# PCB-BI16-1x4.net
KiCad netlist of a schematic drawn in EAGLE
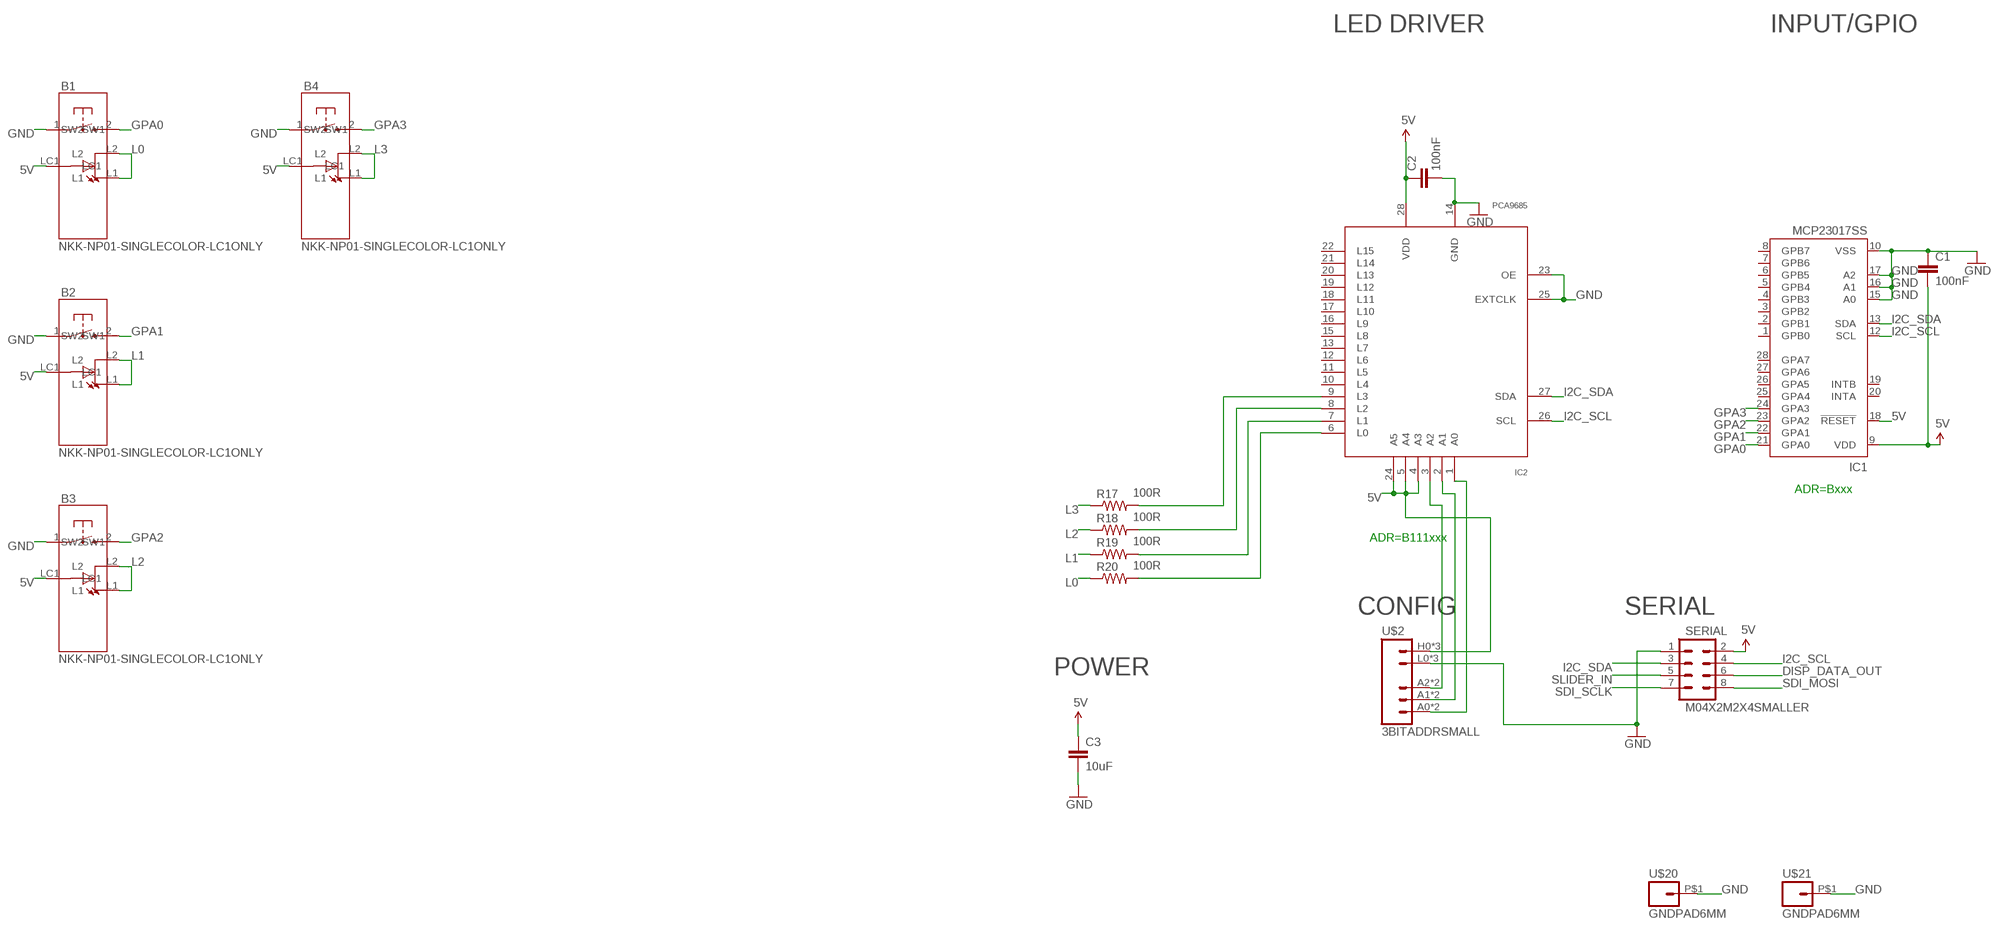
[diagram p0: schematic, sheet 1]

(export (version "E")
  (design (tool "Eeschema 10.0.6"))
  (components
    (comp (ref "B1")
      (value "NKK-NP01-SINGLECOLOR-LC1ONLY")
      (footprint "eagle-import:NKK-NP01_LESSHOLES2")
      (libsource (lib "eagle-import") (part "NKK-NP01-SINGLECOLOR-LC1ONLY"))
    )
    (comp (ref "B2")
      (value "NKK-NP01-SINGLECOLOR-LC1ONLY")
      (footprint "eagle-import:NKK-NP01_LESSHOLES2")
      (libsource (lib "eagle-import") (part "NKK-NP01-SINGLECOLOR-LC1ONLY"))
    )
    (comp (ref "B3")
      (value "NKK-NP01-SINGLECOLOR-LC1ONLY")
      (footprint "eagle-import:NKK-NP01_LESSHOLES2")
      (libsource (lib "eagle-import") (part "NKK-NP01-SINGLECOLOR-LC1ONLY"))
    )
    (comp (ref "B4")
      (value "NKK-NP01-SINGLECOLOR-LC1ONLY")
      (footprint "eagle-import:NKK-NP01_LESSHOLES2")
      (libsource (lib "eagle-import") (part "NKK-NP01-SINGLECOLOR-LC1ONLY"))
    )
    (comp (ref "C1")
      (value "100nF")
      (footprint "eagle-import:0603-CAP")
      (libsource (lib "eagle-import") (part "CAP0603-CAP"))
    )
    (comp (ref "C2")
      (value "100nF")
      (footprint "eagle-import:0603-CAP")
      (libsource (lib "eagle-import") (part "CAP0603-CAP"))
    )
    (comp (ref "C3")
      (value "10uF")
      (footprint "eagle-import:0805")
      (libsource (lib "eagle-import") (part "CAP0805"))
    )
    (comp (ref "IC1")
      (value "MCP23017SS")
      (footprint "eagle-import:SSOP28")
      (fields
        (field (name "MF") "MICROCHIP")
        (field (name "MPN") "MCP23017-E/SS")
        (field (name "MPN_1") "MCP23017-E/SS")
        (field (name "OC_FARNELL") "1467674")
        (field (name "OC_NEWARK") "31K2960")
      )
      (libsource (lib "eagle-import") (part "MCP23017SS"))
    )
    (comp (ref "IC2")
      (value "PCA9685")
      (footprint "eagle-import:TSSOP28")
      (libsource (lib "eagle-import") (part "PCA9685"))
    )
    (comp (ref "R17")
      (value "100R")
      (footprint "eagle-import:0603-RES")
      (libsource (lib "eagle-import") (part "RESISTOR0603-RES"))
    )
    (comp (ref "R18")
      (value "100R")
      (footprint "eagle-import:0603-RES")
      (libsource (lib "eagle-import") (part "RESISTOR0603-RES"))
    )
    (comp (ref "R19")
      (value "100R")
      (footprint "eagle-import:0603-RES")
      (libsource (lib "eagle-import") (part "RESISTOR0603-RES"))
    )
    (comp (ref "R20")
      (value "100R")
      (footprint "eagle-import:0603-RES")
      (libsource (lib "eagle-import") (part "RESISTOR0603-RES"))
    )
    (comp (ref "SERIAL")
      (value "M04X2M2X4SMALLER")
      (footprint "eagle-import:M2X4SMALLER")
      (libsource (lib "eagle-import") (part "M04X2M2X4SMALLER"))
    )
    (comp (ref "U$2")
      (value "3BITADDRSMALL")
      (footprint "eagle-import:3BITADDR_SMALL")
      (libsource (lib "eagle-import") (part "3BITADDRSMALL"))
    )
    (comp (ref "U$20")
      (value "GNDPAD6MM")
      (footprint "eagle-import:3.2MMPAD6MM")
      (libsource (lib "eagle-import") (part "GNDPAD6MM"))
    )
    (comp (ref "U$21")
      (value "GNDPAD6MM")
      (footprint "eagle-import:3.2MMPAD6MM")
      (libsource (lib "eagle-import") (part "GNDPAD6MM"))
    )
  )
  (nets
    (net (code "1") (name "5V") (class "Default")
      (node (ref "B1") (pin "LC1") (pinfunction "LC1_LC1") (pintype "bidirectional"))
      (node (ref "B2") (pin "LC1") (pinfunction "LC1_LC1") (pintype "bidirectional"))
      (node (ref "B3") (pin "LC1") (pinfunction "LC1_LC1") (pintype "bidirectional"))
      (node (ref "B4") (pin "LC1") (pinfunction "LC1_LC1") (pintype "bidirectional"))
      (node (ref "C1") (pin "2") (pinfunction "2_2") (pintype "passive"))
      (node (ref "C2") (pin "1") (pinfunction "1_1") (pintype "passive"))
      (node (ref "C3") (pin "1") (pinfunction "1_1") (pintype "passive"))
      (node (ref "IC1") (pin "18") (pinfunction "~{RESET}_18") (pintype "input"))
      (node (ref "IC1") (pin "9") (pinfunction "VDD_9") (pintype "power_in"))
      (node (ref "IC2") (pin "24") (pinfunction "A5_24") (pintype "input"))
      (node (ref "IC2") (pin "28") (pinfunction "VDD_28") (pintype "power_in"))
      (node (ref "IC2") (pin "4") (pinfunction "A3_4") (pintype "input"))
      (node (ref "IC2") (pin "5") (pinfunction "A4_5") (pintype "input"))
      (node (ref "SERIAL") (pin "2") (pinfunction "2_2") (pintype "passive"))
      (node (ref "U$2") (pin "H0") (pinfunction "VCC_H0") (pintype "passive"))
      (node (ref "U$2") (pin "H1") (pinfunction "VCC_H1") (pintype "passive"))
      (node (ref "U$2") (pin "H2") (pinfunction "VCC_H2") (pintype "passive"))
    )
    (net (code "2") (name "DISP_DATA_OUT") (class "Default")
      (node (ref "SERIAL") (pin "6") (pinfunction "6_6") (pintype "passive"))
    )
    (net (code "3") (name "GND") (class "Default")
      (node (ref "B1") (pin "1") (pinfunction "SW1_1") (pintype "bidirectional"))
      (node (ref "B2") (pin "1") (pinfunction "SW1_1") (pintype "bidirectional"))
      (node (ref "B3") (pin "1") (pinfunction "SW1_1") (pintype "bidirectional"))
      (node (ref "B4") (pin "1") (pinfunction "SW1_1") (pintype "bidirectional"))
      (node (ref "C1") (pin "1") (pinfunction "1_1") (pintype "passive"))
      (node (ref "C2") (pin "2") (pinfunction "2_2") (pintype "passive"))
      (node (ref "C3") (pin "2") (pinfunction "2_2") (pintype "passive"))
      (node (ref "IC1") (pin "10") (pinfunction "VSS_10") (pintype "power_in"))
      (node (ref "IC1") (pin "15") (pinfunction "A0_15") (pintype "input"))
      (node (ref "IC1") (pin "16") (pinfunction "A1_16") (pintype "input"))
      (node (ref "IC1") (pin "17") (pinfunction "A2_17") (pintype "input"))
      (node (ref "IC2") (pin "14") (pinfunction "GND_14") (pintype "power_in"))
      (node (ref "IC2") (pin "23") (pinfunction "OE_23") (pintype "input"))
      (node (ref "IC2") (pin "25") (pinfunction "EXTCLK_25") (pintype "input"))
      (node (ref "SERIAL") (pin "1") (pinfunction "1_1") (pintype "passive"))
      (node (ref "U$2") (pin "L0") (pinfunction "GND_L0") (pintype "passive"))
      (node (ref "U$2") (pin "L1") (pinfunction "GND_L1") (pintype "passive"))
      (node (ref "U$2") (pin "L2") (pinfunction "GND_L2") (pintype "passive"))
      (node (ref "U$20") (pin "P$1") (pinfunction "1_P$1") (pintype "passive"))
      (node (ref "U$21") (pin "P$1") (pinfunction "1_P$1") (pintype "passive"))
    )
    (net (code "4") (name "GPA0") (class "Default")
      (node (ref "B1") (pin "2") (pinfunction "SW2_2") (pintype "bidirectional"))
      (node (ref "IC1") (pin "21") (pinfunction "GPA0_21") (pintype "bidirectional"))
    )
    (net (code "5") (name "GPA1") (class "Default")
      (node (ref "B2") (pin "2") (pinfunction "SW2_2") (pintype "bidirectional"))
      (node (ref "IC1") (pin "22") (pinfunction "GPA1_22") (pintype "bidirectional"))
    )
    (net (code "6") (name "GPA2") (class "Default")
      (node (ref "B3") (pin "2") (pinfunction "SW2_2") (pintype "bidirectional"))
      (node (ref "IC1") (pin "23") (pinfunction "GPA2_23") (pintype "bidirectional"))
    )
    (net (code "7") (name "GPA3") (class "Default")
      (node (ref "B4") (pin "2") (pinfunction "SW2_2") (pintype "bidirectional"))
      (node (ref "IC1") (pin "24") (pinfunction "GPA3_24") (pintype "bidirectional"))
    )
    (net (code "8") (name "I2C_SCL") (class "Default")
      (node (ref "IC1") (pin "12") (pinfunction "SCL_12") (pintype "input"))
      (node (ref "IC2") (pin "26") (pinfunction "SCL_26") (pintype "input"))
      (node (ref "SERIAL") (pin "4") (pinfunction "4_4") (pintype "passive"))
    )
    (net (code "9") (name "I2C_SDA") (class "Default")
      (node (ref "IC1") (pin "13") (pinfunction "SDA_13") (pintype "bidirectional"))
      (node (ref "IC2") (pin "27") (pinfunction "SDA_27") (pintype "input"))
      (node (ref "SERIAL") (pin "3") (pinfunction "3_3") (pintype "passive"))
    )
    (net (code "10") (name "L0") (class "Default")
      (node (ref "B1") (pin "L1") (pinfunction "L1_L1") (pintype "bidirectional"))
      (node (ref "B1") (pin "L2") (pinfunction "L2_L2") (pintype "bidirectional"))
      (node (ref "R20") (pin "1") (pinfunction "1_1") (pintype "passive"))
    )
    (net (code "11") (name "L1") (class "Default")
      (node (ref "B2") (pin "L1") (pinfunction "L1_L1") (pintype "bidirectional"))
      (node (ref "B2") (pin "L2") (pinfunction "L2_L2") (pintype "bidirectional"))
      (node (ref "R19") (pin "1") (pinfunction "1_1") (pintype "passive"))
    )
    (net (code "12") (name "L2") (class "Default")
      (node (ref "B3") (pin "L1") (pinfunction "L1_L1") (pintype "bidirectional"))
      (node (ref "B3") (pin "L2") (pinfunction "L2_L2") (pintype "bidirectional"))
      (node (ref "R18") (pin "1") (pinfunction "1_1") (pintype "passive"))
    )
    (net (code "13") (name "L3") (class "Default")
      (node (ref "B4") (pin "L1") (pinfunction "L1_L1") (pintype "bidirectional"))
      (node (ref "B4") (pin "L2") (pinfunction "L2_L2") (pintype "bidirectional"))
      (node (ref "R17") (pin "1") (pinfunction "1_1") (pintype "passive"))
    )
    (net (code "14") (name "Net-(IC2-A0)") (class "Default")
      (node (ref "IC2") (pin "1") (pinfunction "A0_1") (pintype "input"))
      (node (ref "U$2") (pin "A0") (pinfunction "A0_A0") (pintype "passive"))
      (node (ref "U$2") (pin "AS0") (pinfunction "A0_AS0") (pintype "passive"))
    )
    (net (code "15") (name "Net-(IC2-A1)") (class "Default")
      (node (ref "IC2") (pin "2") (pinfunction "A1_2") (pintype "input"))
      (node (ref "U$2") (pin "A1") (pinfunction "A1_A1") (pintype "passive"))
      (node (ref "U$2") (pin "AS1") (pinfunction "A1_AS1") (pintype "passive"))
    )
    (net (code "16") (name "Net-(IC2-A2)") (class "Default")
      (node (ref "IC2") (pin "3") (pinfunction "A2_3") (pintype "input"))
      (node (ref "U$2") (pin "A2") (pinfunction "A2_A2") (pintype "passive"))
      (node (ref "U$2") (pin "AS2") (pinfunction "A2_AS2") (pintype "passive"))
    )
    (net (code "17") (name "Net-(IC2-L0)") (class "Default")
      (node (ref "IC2") (pin "6") (pinfunction "L0_6") (pintype "output"))
      (node (ref "R20") (pin "2") (pinfunction "2_2") (pintype "passive"))
    )
    (net (code "18") (name "Net-(IC2-L1)") (class "Default")
      (node (ref "IC2") (pin "7") (pinfunction "L1_7") (pintype "output"))
      (node (ref "R19") (pin "2") (pinfunction "2_2") (pintype "passive"))
    )
    (net (code "19") (name "Net-(IC2-L2)") (class "Default")
      (node (ref "IC2") (pin "8") (pinfunction "L2_8") (pintype "output"))
      (node (ref "R18") (pin "2") (pinfunction "2_2") (pintype "passive"))
    )
    (net (code "20") (name "Net-(IC2-L3)") (class "Default")
      (node (ref "IC2") (pin "9") (pinfunction "L3_9") (pintype "output"))
      (node (ref "R17") (pin "2") (pinfunction "2_2") (pintype "passive"))
    )
    (net (code "21") (name "SDI_MOSI") (class "Default")
      (node (ref "SERIAL") (pin "8") (pinfunction "8_8") (pintype "passive"))
    )
    (net (code "22") (name "SDI_SCLK") (class "Default")
      (node (ref "SERIAL") (pin "7") (pinfunction "7_7") (pintype "passive"))
    )
    (net (code "23") (name "SLIDER_IN") (class "Default")
      (node (ref "SERIAL") (pin "5") (pinfunction "5_5") (pintype "passive"))
    )
    (net (code "24") (name "unconnected-(IC1-GPA4-Pad25)") (class "Default")
      (node (ref "IC1") (pin "25") (pinfunction "GPA4_25") (pintype "bidirectional"))
    )
    (net (code "25") (name "unconnected-(IC1-GPA5-Pad26)") (class "Default")
      (node (ref "IC1") (pin "26") (pinfunction "GPA5_26") (pintype "bidirectional"))
    )
    (net (code "26") (name "unconnected-(IC1-GPA6-Pad27)") (class "Default")
      (node (ref "IC1") (pin "27") (pinfunction "GPA6_27") (pintype "bidirectional"))
    )
    (net (code "27") (name "unconnected-(IC1-GPA7-Pad28)") (class "Default")
      (node (ref "IC1") (pin "28") (pinfunction "GPA7_28") (pintype "bidirectional"))
    )
    (net (code "28") (name "unconnected-(IC1-GPB0-Pad1)") (class "Default")
      (node (ref "IC1") (pin "1") (pinfunction "GPB0_1") (pintype "bidirectional"))
    )
    (net (code "29") (name "unconnected-(IC1-GPB1-Pad2)") (class "Default")
      (node (ref "IC1") (pin "2") (pinfunction "GPB1_2") (pintype "bidirectional"))
    )
    (net (code "30") (name "unconnected-(IC1-GPB2-Pad3)") (class "Default")
      (node (ref "IC1") (pin "3") (pinfunction "GPB2_3") (pintype "bidirectional"))
    )
    (net (code "31") (name "unconnected-(IC1-GPB3-Pad4)") (class "Default")
      (node (ref "IC1") (pin "4") (pinfunction "GPB3_4") (pintype "bidirectional"))
    )
    (net (code "32") (name "unconnected-(IC1-GPB4-Pad5)") (class "Default")
      (node (ref "IC1") (pin "5") (pinfunction "GPB4_5") (pintype "bidirectional"))
    )
    (net (code "33") (name "unconnected-(IC1-GPB5-Pad6)") (class "Default")
      (node (ref "IC1") (pin "6") (pinfunction "GPB5_6") (pintype "bidirectional"))
    )
    (net (code "34") (name "unconnected-(IC1-GPB6-Pad7)") (class "Default")
      (node (ref "IC1") (pin "7") (pinfunction "GPB6_7") (pintype "bidirectional"))
    )
    (net (code "35") (name "unconnected-(IC1-GPB7-Pad8)") (class "Default")
      (node (ref "IC1") (pin "8") (pinfunction "GPB7_8") (pintype "bidirectional"))
    )
    (net (code "36") (name "unconnected-(IC1-INTA-Pad20)") (class "Default")
      (node (ref "IC1") (pin "20") (pinfunction "INTA_20") (pintype "output"))
    )
    (net (code "37") (name "unconnected-(IC1-INTB-Pad19)") (class "Default")
      (node (ref "IC1") (pin "19") (pinfunction "INTB_19") (pintype "output"))
    )
    (net (code "38") (name "unconnected-(IC2-L4-Pad10)") (class "Default")
      (node (ref "IC2") (pin "10") (pinfunction "L4_10") (pintype "output"))
    )
    (net (code "39") (name "unconnected-(IC2-L5-Pad11)") (class "Default")
      (node (ref "IC2") (pin "11") (pinfunction "L5_11") (pintype "output"))
    )
    (net (code "40") (name "unconnected-(IC2-L6-Pad12)") (class "Default")
      (node (ref "IC2") (pin "12") (pinfunction "L6_12") (pintype "output"))
    )
    (net (code "41") (name "unconnected-(IC2-L7-Pad13)") (class "Default")
      (node (ref "IC2") (pin "13") (pinfunction "L7_13") (pintype "output"))
    )
    (net (code "42") (name "unconnected-(IC2-L8-Pad15)") (class "Default")
      (node (ref "IC2") (pin "15") (pinfunction "L8_15") (pintype "output"))
    )
    (net (code "43") (name "unconnected-(IC2-L9-Pad16)") (class "Default")
      (node (ref "IC2") (pin "16") (pinfunction "L9_16") (pintype "output"))
    )
    (net (code "44") (name "unconnected-(IC2-L10-Pad17)") (class "Default")
      (node (ref "IC2") (pin "17") (pinfunction "L10_17") (pintype "output"))
    )
    (net (code "45") (name "unconnected-(IC2-L11-Pad18)") (class "Default")
      (node (ref "IC2") (pin "18") (pinfunction "L11_18") (pintype "output"))
    )
    (net (code "46") (name "unconnected-(IC2-L12-Pad19)") (class "Default")
      (node (ref "IC2") (pin "19") (pinfunction "L12_19") (pintype "output"))
    )
    (net (code "47") (name "unconnected-(IC2-L13-Pad20)") (class "Default")
      (node (ref "IC2") (pin "20") (pinfunction "L13_20") (pintype "output"))
    )
    (net (code "48") (name "unconnected-(IC2-L14-Pad21)") (class "Default")
      (node (ref "IC2") (pin "21") (pinfunction "L14_21") (pintype "output"))
    )
    (net (code "49") (name "unconnected-(IC2-L15-Pad22)") (class "Default")
      (node (ref "IC2") (pin "22") (pinfunction "L15_22") (pintype "output"))
    )
  )
)
